# vga-sync-separator2-3_3V.net
KiCad netlist of a schematic drawn in EAGLE
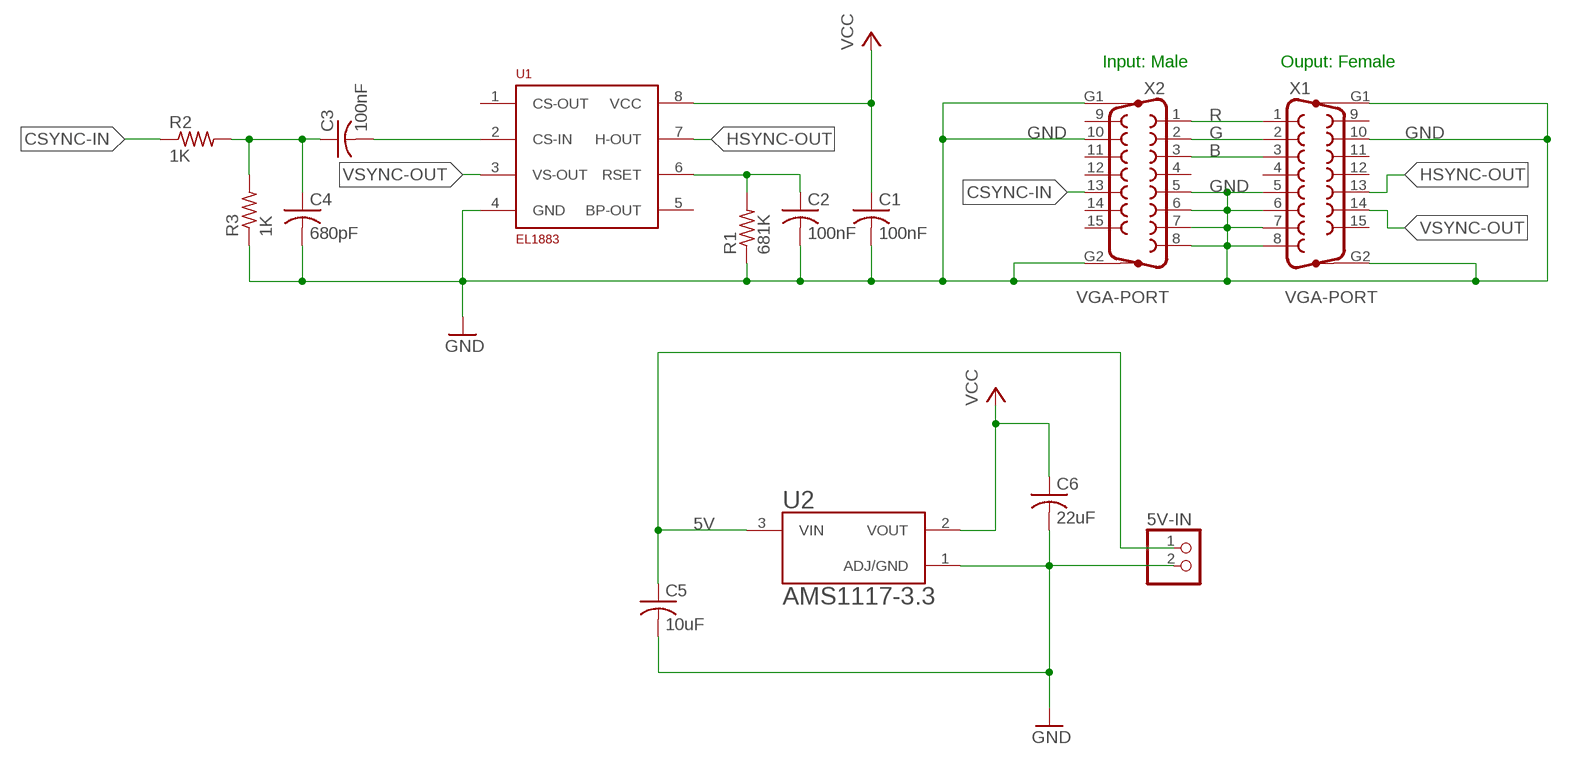
[diagram p0: schematic, sheet 1]

(export (version "E")
  (design (tool "Eeschema 10.0.6"))
  (components
    (comp (ref "5V-IN")
      (value "PINHD-1X2")
      (footprint "eagle-import:1X02")
      (libsource (lib "eagle-import") (part "PINHD-1X2"))
    )
    (comp (ref "C1")
      (value "100nF")
      (footprint "eagle-import:C0805")
      (libsource (lib "eagle-import") (part "C-USC0805"))
    )
    (comp (ref "C2")
      (value "100nF")
      (footprint "eagle-import:C0805")
      (libsource (lib "eagle-import") (part "C-USC0805"))
    )
    (comp (ref "C3")
      (value "100nF")
      (footprint "eagle-import:C0805")
      (libsource (lib "eagle-import") (part "C-USC0805"))
    )
    (comp (ref "C4")
      (value "680pF")
      (footprint "eagle-import:C0805")
      (libsource (lib "eagle-import") (part "C-USC0805"))
    )
    (comp (ref "C5")
      (value "10uF")
      (footprint "eagle-import:C0805")
      (libsource (lib "eagle-import") (part "C-USC0805"))
    )
    (comp (ref "C6")
      (value "22uF")
      (footprint "eagle-import:C0805")
      (libsource (lib "eagle-import") (part "C-USC0805"))
    )
    (comp (ref "R1")
      (value "681K")
      (footprint "eagle-import:R0805")
      (libsource (lib "eagle-import") (part "R-US_R0805"))
    )
    (comp (ref "R2")
      (value "1K")
      (footprint "eagle-import:R0805")
      (libsource (lib "eagle-import") (part "R-US_R0805"))
    )
    (comp (ref "R3")
      (value "1K")
      (footprint "eagle-import:R0805")
      (libsource (lib "eagle-import") (part "R-US_R0805"))
    )
    (comp (ref "U1")
      (value "EL1883")
      (footprint "eagle-import:SO-8")
      (libsource (lib "eagle-import") (part "EL1883"))
    )
    (comp (ref "U2")
      (value "AMS1117-3.3")
      (footprint "eagle-import:SOT229P700X180-4N")
      (fields (field (name "MF") "Advanced Monolithic Systems"))
      (libsource (lib "eagle-import") (part "AMS1117-3.3"))
    )
    (comp (ref "X1")
      (value "VGA-PORT")
      (footprint "eagle-import:HD15H")
      (libsource (lib "eagle-import") (part "VGA-PORT"))
    )
    (comp (ref "X2")
      (value "VGA-PORT")
      (footprint "eagle-import:HD15H")
      (libsource (lib "eagle-import") (part "VGA-PORT"))
    )
  )
  (nets
    (net (code "1") (name "/5V") (class "Default")
      (node (ref "5V-IN") (pin "1") (pinfunction "1_1") (pintype "passive"))
      (node (ref "C5") (pin "1") (pinfunction "1_1") (pintype "passive"))
      (node (ref "U2") (pin "3") (pinfunction "VIN_3") (pintype "input"))
    )
    (net (code "2") (name "/B") (class "Default")
      (node (ref "X1") (pin "3") (pinfunction "3_3") (pintype "passive"))
      (node (ref "X2") (pin "3") (pinfunction "3_3") (pintype "passive"))
    )
    (net (code "3") (name "/G") (class "Default")
      (node (ref "X1") (pin "2") (pinfunction "2_2") (pintype "passive"))
      (node (ref "X2") (pin "2") (pinfunction "2_2") (pintype "passive"))
    )
    (net (code "4") (name "/R") (class "Default")
      (node (ref "X1") (pin "1") (pinfunction "1_1") (pintype "passive"))
      (node (ref "X2") (pin "1") (pinfunction "1_1") (pintype "passive"))
    )
    (net (code "5") (name "CSYNC-IN") (class "Default")
      (node (ref "R2") (pin "1") (pinfunction "1_1") (pintype "passive"))
      (node (ref "X2") (pin "13") (pinfunction "13_13") (pintype "passive"))
    )
    (net (code "6") (name "GND") (class "Default")
      (node (ref "5V-IN") (pin "2") (pinfunction "2_2") (pintype "passive"))
      (node (ref "C1") (pin "2") (pinfunction "2_2") (pintype "passive"))
      (node (ref "C2") (pin "2") (pinfunction "2_2") (pintype "passive"))
      (node (ref "C4") (pin "2") (pinfunction "2_2") (pintype "passive"))
      (node (ref "C5") (pin "2") (pinfunction "2_2") (pintype "passive"))
      (node (ref "C6") (pin "2") (pinfunction "2_2") (pintype "passive"))
      (node (ref "R1") (pin "1") (pinfunction "1_1") (pintype "passive"))
      (node (ref "R3") (pin "1") (pinfunction "1_1") (pintype "passive"))
      (node (ref "U1") (pin "4") (pinfunction "GND_4") (pintype "bidirectional"))
      (node (ref "U2") (pin "1") (pinfunction "ADJ/GND_1") (pintype "power_in"))
      (node (ref "X1") (pin "10") (pinfunction "10_10") (pintype "passive"))
      (node (ref "X1") (pin "5") (pinfunction "5_5") (pintype "passive"))
      (node (ref "X1") (pin "6") (pinfunction "6_6") (pintype "passive"))
      (node (ref "X1") (pin "7") (pinfunction "7_7") (pintype "passive"))
      (node (ref "X1") (pin "8") (pinfunction "8_8") (pintype "passive"))
      (node (ref "X1") (pin "G1") (pinfunction "G1_G1") (pintype "passive"))
      (node (ref "X1") (pin "G2") (pinfunction "G2_G2") (pintype "passive"))
      (node (ref "X2") (pin "10") (pinfunction "10_10") (pintype "passive"))
      (node (ref "X2") (pin "5") (pinfunction "5_5") (pintype "passive"))
      (node (ref "X2") (pin "6") (pinfunction "6_6") (pintype "passive"))
      (node (ref "X2") (pin "7") (pinfunction "7_7") (pintype "passive"))
      (node (ref "X2") (pin "8") (pinfunction "8_8") (pintype "passive"))
      (node (ref "X2") (pin "G1") (pinfunction "G1_G1") (pintype "passive"))
      (node (ref "X2") (pin "G2") (pinfunction "G2_G2") (pintype "passive"))
    )
    (net (code "7") (name "HSYNC-OUT") (class "Default")
      (node (ref "U1") (pin "7") (pinfunction "H-OUT_7") (pintype "bidirectional"))
      (node (ref "X1") (pin "13") (pinfunction "13_13") (pintype "passive"))
    )
    (net (code "8") (name "Net-(C3-Pad1)") (class "Default")
      (node (ref "C3") (pin "1") (pinfunction "1_1") (pintype "passive"))
      (node (ref "C4") (pin "1") (pinfunction "1_1") (pintype "passive"))
      (node (ref "R2") (pin "2") (pinfunction "2_2") (pintype "passive"))
      (node (ref "R3") (pin "2") (pinfunction "2_2") (pintype "passive"))
    )
    (net (code "9") (name "Net-(U1-CS-IN)") (class "Default")
      (node (ref "C3") (pin "2") (pinfunction "2_2") (pintype "passive"))
      (node (ref "U1") (pin "2") (pinfunction "CS-IN_2") (pintype "bidirectional"))
    )
    (net (code "10") (name "Net-(U1-RSET)") (class "Default")
      (node (ref "C2") (pin "1") (pinfunction "1_1") (pintype "passive"))
      (node (ref "R1") (pin "2") (pinfunction "2_2") (pintype "passive"))
      (node (ref "U1") (pin "6") (pinfunction "RSET_6") (pintype "bidirectional"))
    )
    (net (code "11") (name "VCC") (class "Default")
      (node (ref "C1") (pin "1") (pinfunction "1_1") (pintype "passive"))
      (node (ref "C6") (pin "1") (pinfunction "1_1") (pintype "passive"))
      (node (ref "U1") (pin "8") (pinfunction "VCC_8") (pintype "bidirectional"))
      (node (ref "U2") (pin "2") (pinfunction "VOUT_2") (pintype "output"))
    )
    (net (code "12") (name "VSYNC-OUT") (class "Default")
      (node (ref "U1") (pin "3") (pinfunction "VS-OUT_3") (pintype "bidirectional"))
      (node (ref "X1") (pin "14") (pinfunction "14_14") (pintype "passive"))
    )
    (net (code "13") (name "unconnected-(U1-BP-OUT-Pad5)") (class "Default")
      (node (ref "U1") (pin "5") (pinfunction "BP-OUT_5") (pintype "bidirectional"))
    )
    (net (code "14") (name "unconnected-(U1-CS-OUT-Pad1)") (class "Default")
      (node (ref "U1") (pin "1") (pinfunction "CS-OUT_1") (pintype "bidirectional"))
    )
    (net (code "15") (name "unconnected-(X1-Pad4)") (class "Default")
      (node (ref "X1") (pin "4") (pinfunction "4_4") (pintype "passive"))
    )
    (net (code "16") (name "unconnected-(X1-Pad9)") (class "Default")
      (node (ref "X1") (pin "9") (pinfunction "9_9") (pintype "passive"))
    )
    (net (code "17") (name "unconnected-(X1-Pad11)") (class "Default")
      (node (ref "X1") (pin "11") (pinfunction "11_11") (pintype "passive"))
    )
    (net (code "18") (name "unconnected-(X1-Pad12)") (class "Default")
      (node (ref "X1") (pin "12") (pinfunction "12_12") (pintype "passive"))
    )
    (net (code "19") (name "unconnected-(X1-Pad15)") (class "Default")
      (node (ref "X1") (pin "15") (pinfunction "15_15") (pintype "passive"))
    )
    (net (code "20") (name "unconnected-(X2-Pad4)") (class "Default")
      (node (ref "X2") (pin "4") (pinfunction "4_4") (pintype "passive"))
    )
    (net (code "21") (name "unconnected-(X2-Pad9)") (class "Default")
      (node (ref "X2") (pin "9") (pinfunction "9_9") (pintype "passive"))
    )
    (net (code "22") (name "unconnected-(X2-Pad11)") (class "Default")
      (node (ref "X2") (pin "11") (pinfunction "11_11") (pintype "passive"))
    )
    (net (code "23") (name "unconnected-(X2-Pad12)") (class "Default")
      (node (ref "X2") (pin "12") (pinfunction "12_12") (pintype "passive"))
    )
    (net (code "24") (name "unconnected-(X2-Pad14)") (class "Default")
      (node (ref "X2") (pin "14") (pinfunction "14_14") (pintype "passive"))
    )
    (net (code "25") (name "unconnected-(X2-Pad15)") (class "Default")
      (node (ref "X2") (pin "15") (pinfunction "15_15") (pintype "passive"))
    )
  )
)
